# circuit.net
KiCad netlist of a schematic drawn in EAGLE
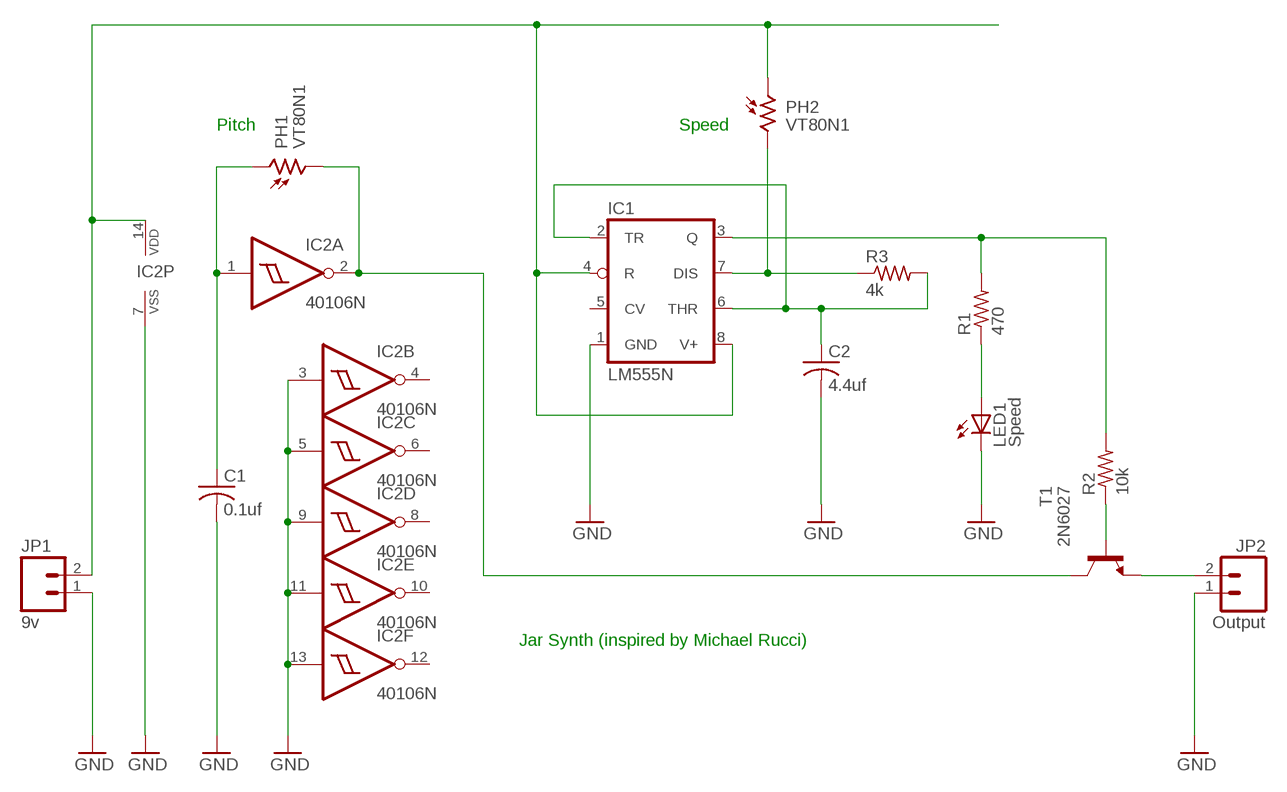
[diagram p0: schematic, sheet 1]

(export (version "E")
  (design (tool "Eeschema 10.0.6"))
  (components
    (comp (ref "C1")
      (value "0.1uf")
      (footprint "eagle-import:C050-025X075")
      (libsource (lib "eagle-import") (part "C-US050-025X075"))
    )
    (comp (ref "C2")
      (value "4.4uf")
      (footprint "eagle-import:C050-025X075")
      (libsource (lib "eagle-import") (part "C-US050-025X075"))
    )
    (comp (ref "IC1")
      (value "LM555N")
      (footprint "eagle-import:DIL08")
      (libsource (lib "eagle-import") (part "555NLM"))
    )
    (comp (ref "IC2")
      (value "40106N")
      (footprint "eagle-import:DIL14")
      (libsource (lib "eagle-import") (part "40106N"))
    )
    (comp (ref "JP1")
      (value "9v")
      (footprint "eagle-import:1X02")
      (libsource (lib "eagle-import") (part "M02PTH"))
    )
    (comp (ref "JP2")
      (value "Output")
      (footprint "eagle-import:1X02")
      (libsource (lib "eagle-import") (part "M02PTH"))
    )
    (comp (ref "LED1")
      (value "Speed")
      (footprint "eagle-import:LED5MM")
      (libsource (lib "eagle-import") (part "LED5MM"))
    )
    (comp (ref "PH1")
      (value "VT80N1")
      (footprint "eagle-import:VT800")
      (libsource (lib "eagle-import") (part "VT80N1"))
    )
    (comp (ref "PH2")
      (value "VT80N1")
      (footprint "eagle-import:VT800")
      (libsource (lib "eagle-import") (part "VT80N1"))
    )
    (comp (ref "R1")
      (value "470")
      (footprint "eagle-import:0207_7")
      (libsource (lib "eagle-import") (part "R-US_0207/7"))
    )
    (comp (ref "R2")
      (value "10k")
      (footprint "eagle-import:0207_7")
      (libsource (lib "eagle-import") (part "R-US_0207/7"))
    )
    (comp (ref "R3")
      (value "4k")
      (footprint "eagle-import:0207_7")
      (libsource (lib "eagle-import") (part "R-US_0207/7"))
    )
    (comp (ref "T1")
      (value "2N6027")
      (footprint "eagle-import:TO92-ECB")
      (libsource (lib "eagle-import") (part "2SC458"))
    )
  )
  (nets
    (net (code "1") (name "GND") (class "Default")
      (node (ref "C1") (pin "2") (pinfunction "2_2") (pintype "passive"))
      (node (ref "C2") (pin "2") (pinfunction "2_2") (pintype "passive"))
      (node (ref "IC1") (pin "1") (pinfunction "GND_1") (pintype "power_in"))
      (node (ref "IC2") (pin "11") (pinfunction "I_11") (pintype "input"))
      (node (ref "IC2") (pin "13") (pinfunction "I_13") (pintype "input"))
      (node (ref "IC2") (pin "3") (pinfunction "I_3") (pintype "input"))
      (node (ref "IC2") (pin "5") (pinfunction "I_5") (pintype "input"))
      (node (ref "IC2") (pin "7") (pinfunction "VSS_7") (pintype "power_in"))
      (node (ref "IC2") (pin "9") (pinfunction "I_9") (pintype "input"))
      (node (ref "JP1") (pin "1") (pinfunction "1_1") (pintype "passive"))
      (node (ref "JP2") (pin "1") (pinfunction "1_1") (pintype "passive"))
      (node (ref "LED1") (pin "K") (pinfunction "C_K") (pintype "passive"))
    )
    (net (code "2") (name "Net-(IC1-DIS)") (class "Default")
      (node (ref "IC1") (pin "7") (pinfunction "DIS_7") (pintype "input"))
      (node (ref "PH2") (pin "2") (pinfunction "2_2") (pintype "passive"))
      (node (ref "R3") (pin "1") (pinfunction "1_1") (pintype "passive"))
    )
    (net (code "3") (name "Net-(IC1-Q)") (class "Default")
      (node (ref "IC1") (pin "3") (pinfunction "Q_3") (pintype "output"))
      (node (ref "R1") (pin "2") (pinfunction "2_2") (pintype "passive"))
      (node (ref "R2") (pin "2") (pinfunction "2_2") (pintype "passive"))
    )
    (net (code "4") (name "Net-(IC1-R)") (class "Default")
      (node (ref "IC1") (pin "4") (pinfunction "R_4") (pintype "input"))
      (node (ref "IC1") (pin "8") (pinfunction "V+_8") (pintype "power_in"))
      (node (ref "IC2") (pin "14") (pinfunction "VDD_14") (pintype "power_in"))
      (node (ref "JP1") (pin "2") (pinfunction "2_2") (pintype "passive"))
      (node (ref "PH2") (pin "1") (pinfunction "1_1") (pintype "passive"))
    )
    (net (code "5") (name "Net-(IC1-THR)") (class "Default")
      (node (ref "C2") (pin "1") (pinfunction "1_1") (pintype "passive"))
      (node (ref "IC1") (pin "2") (pinfunction "TR_2") (pintype "input"))
      (node (ref "IC1") (pin "6") (pinfunction "THR_6") (pintype "input"))
      (node (ref "R3") (pin "2") (pinfunction "2_2") (pintype "passive"))
    )
    (net (code "6") (name "Net-(IC2A-I)") (class "Default")
      (node (ref "C1") (pin "1") (pinfunction "1_1") (pintype "passive"))
      (node (ref "IC2") (pin "1") (pinfunction "I_1") (pintype "input"))
      (node (ref "PH1") (pin "1") (pinfunction "1_1") (pintype "passive"))
    )
    (net (code "7") (name "Net-(IC2A-O)") (class "Default")
      (node (ref "IC2") (pin "2") (pinfunction "O_2") (pintype "output"))
      (node (ref "PH1") (pin "2") (pinfunction "2_2") (pintype "passive"))
      (node (ref "T1") (pin "C") (pinfunction "C_C") (pintype "passive"))
    )
    (net (code "8") (name "Net-(JP2-Pad2)") (class "Default")
      (node (ref "JP2") (pin "2") (pinfunction "2_2") (pintype "passive"))
      (node (ref "T1") (pin "E") (pinfunction "E_E") (pintype "passive"))
    )
    (net (code "9") (name "Net-(LED1-PadA)") (class "Default")
      (node (ref "LED1") (pin "A") (pinfunction "A_A") (pintype "passive"))
      (node (ref "R1") (pin "1") (pinfunction "1_1") (pintype "passive"))
    )
    (net (code "10") (name "Net-(R2-Pad1)") (class "Default")
      (node (ref "R2") (pin "1") (pinfunction "1_1") (pintype "passive"))
      (node (ref "T1") (pin "B") (pinfunction "B_B") (pintype "passive"))
    )
    (net (code "11") (name "unconnected-(IC1-CV-Pad5)") (class "Default")
      (node (ref "IC1") (pin "5") (pinfunction "CV_5") (pintype "input"))
    )
    (net (code "12") (name "unconnected-(IC2B-O-Pad4)") (class "Default")
      (node (ref "IC2") (pin "4") (pinfunction "O_4") (pintype "output"))
    )
    (net (code "13") (name "unconnected-(IC2C-O-Pad6)") (class "Default")
      (node (ref "IC2") (pin "6") (pinfunction "O_6") (pintype "output"))
    )
    (net (code "14") (name "unconnected-(IC2D-O-Pad8)") (class "Default")
      (node (ref "IC2") (pin "8") (pinfunction "O_8") (pintype "output"))
    )
    (net (code "15") (name "unconnected-(IC2E-O-Pad10)") (class "Default")
      (node (ref "IC2") (pin "10") (pinfunction "O_10") (pintype "output"))
    )
    (net (code "16") (name "unconnected-(IC2F-O-Pad12)") (class "Default")
      (node (ref "IC2") (pin "12") (pinfunction "O_12") (pintype "output"))
    )
  )
)
